# USB-UART_FT230XS_double-sided.net
KiCad netlist of a schematic drawn in EAGLE
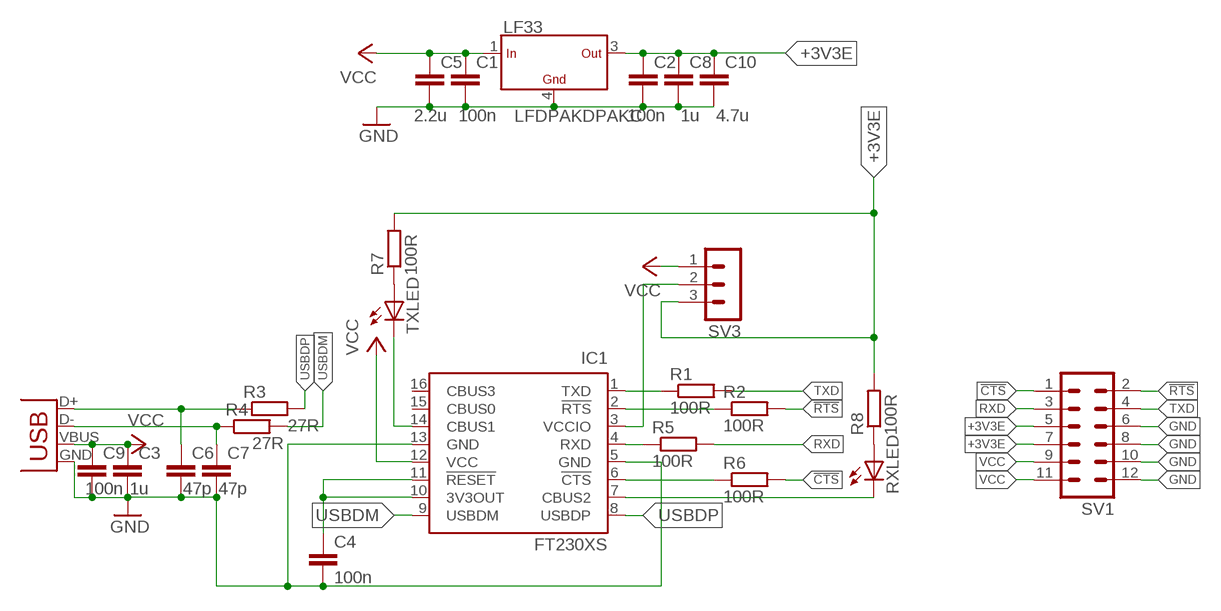
[diagram p0: schematic, sheet 1]

(export (version "E")
  (design (tool "Eeschema 10.0.6"))
  (components
    (comp (ref "C1")
      (value "100n")
      (footprint "eagle-import:C0805")
      (libsource (lib "eagle-import") (part "C-EUC0805"))
    )
    (comp (ref "C2")
      (value "100n")
      (footprint "eagle-import:C0805")
      (libsource (lib "eagle-import") (part "C-EUC0805"))
    )
    (comp (ref "C3")
      (value "1u")
      (footprint "eagle-import:C0805")
      (libsource (lib "eagle-import") (part "C-EUC0805"))
    )
    (comp (ref "C4")
      (value "100n")
      (footprint "eagle-import:C0805")
      (libsource (lib "eagle-import") (part "C-EUC0805"))
    )
    (comp (ref "C5")
      (value "2.2u")
      (footprint "eagle-import:C1206")
      (libsource (lib "eagle-import") (part "C-EUC1206"))
    )
    (comp (ref "C6")
      (value "47p")
      (footprint "eagle-import:C0805")
      (libsource (lib "eagle-import") (part "C-EUC0805"))
    )
    (comp (ref "C7")
      (value "47p")
      (footprint "eagle-import:C0805")
      (libsource (lib "eagle-import") (part "C-EUC0805"))
    )
    (comp (ref "C8")
      (value "1u")
      (footprint "eagle-import:C1206")
      (libsource (lib "eagle-import") (part "C-EUC1206"))
    )
    (comp (ref "C9")
      (value "100n")
      (footprint "eagle-import:C1206")
      (libsource (lib "eagle-import") (part "C-EUC1206"))
    )
    (comp (ref "C10")
      (value "4.7u")
      (footprint "eagle-import:C1206")
      (libsource (lib "eagle-import") (part "C-EUC1206"))
    )
    (comp (ref "IC1")
      (value "FT230XS")
      (footprint "eagle-import:SSOP16")
      (libsource (lib "eagle-import") (part "FT230XS"))
    )
    (comp (ref "LF33")
      (value "LFDPAKDPAKC")
      (footprint "eagle-import:DPAK")
      (libsource (lib "eagle-import") (part "LF??CDPAK"))
    )
    (comp (ref "R1")
      (value "100R")
      (footprint "eagle-import:M0805")
      (libsource (lib "eagle-import") (part "R-EU_M0805"))
    )
    (comp (ref "R2")
      (value "100R")
      (footprint "eagle-import:M0805")
      (libsource (lib "eagle-import") (part "R-EU_M0805"))
    )
    (comp (ref "R3")
      (value "27R")
      (footprint "eagle-import:M0805")
      (libsource (lib "eagle-import") (part "R-EU_M0805"))
    )
    (comp (ref "R4")
      (value "27R")
      (footprint "eagle-import:M0805")
      (libsource (lib "eagle-import") (part "R-EU_M0805"))
    )
    (comp (ref "R5")
      (value "100R")
      (footprint "eagle-import:M0805")
      (libsource (lib "eagle-import") (part "R-EU_M0805"))
    )
    (comp (ref "R6")
      (value "100R")
      (footprint "eagle-import:M0805")
      (libsource (lib "eagle-import") (part "R-EU_M0805"))
    )
    (comp (ref "R7")
      (value "100R")
      (footprint "eagle-import:M0805")
      (libsource (lib "eagle-import") (part "R-EU_M0805"))
    )
    (comp (ref "R8")
      (value "100R")
      (footprint "eagle-import:M0805")
      (libsource (lib "eagle-import") (part "R-EU_M0805"))
    )
    (comp (ref "RXLED")
      (value "LEDCHIP-LED0603")
      (footprint "eagle-import:CHIP-LED0603")
      (libsource (lib "eagle-import") (part "LEDCHIP-LED0603"))
    )
    (comp (ref "SV1")
      (value "MA06-2")
      (footprint "eagle-import:MA06-2")
      (libsource (lib "eagle-import") (part "MA06-2"))
    )
    (comp (ref "SV3")
      (value "MA03-1")
      (footprint "eagle-import:MA03-1")
      (libsource (lib "eagle-import") (part "MA03-1"))
    )
    (comp (ref "TXLED")
      (value "LEDCHIP-LED0603")
      (footprint "eagle-import:CHIP-LED0603")
      (libsource (lib "eagle-import") (part "LEDCHIP-LED0603"))
    )
    (comp (ref "X1")
      (value "USBSMD")
      (footprint "eagle-import:USB-MINIB")
      (libsource (lib "eagle-import") (part "USBSMD"))
    )
  )
  (nets
    (net (code "1") (name "+3V3E") (class "Default")
      (node (ref "C10") (pin "1") (pinfunction "1_1") (pintype "passive"))
      (node (ref "C2") (pin "1") (pinfunction "1_1") (pintype "passive"))
      (node (ref "C8") (pin "1") (pinfunction "1_1") (pintype "passive"))
      (node (ref "LF33") (pin "3") (pinfunction "OUT_3") (pintype "passive"))
      (node (ref "R7") (pin "2") (pinfunction "2_2") (pintype "passive"))
      (node (ref "R8") (pin "2") (pinfunction "2_2") (pintype "passive"))
      (node (ref "SV1") (pin "5") (pinfunction "5_5") (pintype "passive"))
      (node (ref "SV1") (pin "7") (pinfunction "7_7") (pintype "passive"))
      (node (ref "SV3") (pin "3") (pinfunction "3_3") (pintype "passive"))
    )
    (net (code "2") (name "/~{CTS}") (class "Default")
      (node (ref "R6") (pin "2") (pinfunction "2_2") (pintype "passive"))
      (node (ref "SV1") (pin "1") (pinfunction "1_1") (pintype "passive"))
    )
    (net (code "3") (name "/~{RTS}") (class "Default")
      (node (ref "R2") (pin "2") (pinfunction "2_2") (pintype "passive"))
      (node (ref "SV1") (pin "2") (pinfunction "2_2") (pintype "passive"))
    )
    (net (code "4") (name "GND") (class "Default")
      (node (ref "C1") (pin "2") (pinfunction "2_2") (pintype "passive"))
      (node (ref "C10") (pin "2") (pinfunction "2_2") (pintype "passive"))
      (node (ref "C2") (pin "2") (pinfunction "2_2") (pintype "passive"))
      (node (ref "C3") (pin "2") (pinfunction "2_2") (pintype "passive"))
      (node (ref "C4") (pin "2") (pinfunction "2_2") (pintype "passive"))
      (node (ref "C5") (pin "2") (pinfunction "2_2") (pintype "passive"))
      (node (ref "C6") (pin "2") (pinfunction "2_2") (pintype "passive"))
      (node (ref "C7") (pin "2") (pinfunction "2_2") (pintype "passive"))
      (node (ref "C8") (pin "2") (pinfunction "2_2") (pintype "passive"))
      (node (ref "C9") (pin "2") (pinfunction "2_2") (pintype "passive"))
      (node (ref "IC1") (pin "13") (pinfunction "GND_13") (pintype "power_in"))
      (node (ref "IC1") (pin "5") (pinfunction "GND_5") (pintype "power_in"))
      (node (ref "LF33") (pin "4") (pinfunction "GND_4") (pintype "passive"))
      (node (ref "SV1") (pin "10") (pinfunction "10_10") (pintype "passive"))
      (node (ref "SV1") (pin "12") (pinfunction "12_12") (pintype "passive"))
      (node (ref "SV1") (pin "6") (pinfunction "6_6") (pintype "passive"))
      (node (ref "SV1") (pin "8") (pinfunction "8_8") (pintype "passive"))
      (node (ref "X1") (pin "GND") (pinfunction "GND_GND") (pintype "bidirectional"))
    )
    (net (code "5") (name "Net-(C6-Pad1)") (class "Default")
      (node (ref "C6") (pin "1") (pinfunction "1_1") (pintype "passive"))
      (node (ref "R3") (pin "1") (pinfunction "1_1") (pintype "passive"))
      (node (ref "X1") (pin "D+") (pinfunction "D+_D+") (pintype "bidirectional"))
    )
    (net (code "6") (name "Net-(C7-Pad1)") (class "Default")
      (node (ref "C7") (pin "1") (pinfunction "1_1") (pintype "passive"))
      (node (ref "R4") (pin "1") (pinfunction "1_1") (pintype "passive"))
      (node (ref "X1") (pin "D-") (pinfunction "D-_D-") (pintype "bidirectional"))
    )
    (net (code "7") (name "Net-(IC1-3V3OUT)") (class "Default")
      (node (ref "C4") (pin "1") (pinfunction "1_1") (pintype "passive"))
      (node (ref "IC1") (pin "10") (pinfunction "3V3OUT_10") (pintype "output"))
      (node (ref "IC1") (pin "11") (pinfunction "~{RESET}_11") (pintype "input"))
    )
    (net (code "8") (name "Net-(IC1-CBUS1)") (class "Default")
      (node (ref "IC1") (pin "14") (pinfunction "CBUS1_14") (pintype "bidirectional"))
      (node (ref "TXLED") (pin "C") (pinfunction "C_C") (pintype "passive"))
    )
    (net (code "9") (name "Net-(IC1-CBUS2)") (class "Default")
      (node (ref "IC1") (pin "7") (pinfunction "CBUS2_7") (pintype "bidirectional"))
      (node (ref "RXLED") (pin "C") (pinfunction "C_C") (pintype "passive"))
    )
    (net (code "10") (name "Net-(IC1-RXD)") (class "Default")
      (node (ref "IC1") (pin "4") (pinfunction "RXD_4") (pintype "input"))
      (node (ref "R5") (pin "1") (pinfunction "1_1") (pintype "passive"))
    )
    (net (code "11") (name "Net-(IC1-TXD)") (class "Default")
      (node (ref "IC1") (pin "1") (pinfunction "TXD_1") (pintype "output"))
      (node (ref "R1") (pin "1") (pinfunction "1_1") (pintype "passive"))
    )
    (net (code "12") (name "Net-(IC1-VCCIO)") (class "Default")
      (node (ref "IC1") (pin "3") (pinfunction "VCCIO_3") (pintype "power_in"))
      (node (ref "SV3") (pin "2") (pinfunction "2_2") (pintype "passive"))
    )
    (net (code "13") (name "Net-(IC1-~{CTS})") (class "Default")
      (node (ref "IC1") (pin "6") (pinfunction "~{CTS}_6") (pintype "input"))
      (node (ref "R6") (pin "1") (pinfunction "1_1") (pintype "passive"))
    )
    (net (code "14") (name "Net-(IC1-~{RTS})") (class "Default")
      (node (ref "IC1") (pin "2") (pinfunction "~{RTS}_2") (pintype "output"))
      (node (ref "R2") (pin "1") (pinfunction "1_1") (pintype "passive"))
    )
    (net (code "15") (name "Net-(R7-Pad1)") (class "Default")
      (node (ref "R7") (pin "1") (pinfunction "1_1") (pintype "passive"))
      (node (ref "TXLED") (pin "A") (pinfunction "A_A") (pintype "passive"))
    )
    (net (code "16") (name "Net-(R8-Pad1)") (class "Default")
      (node (ref "R8") (pin "1") (pinfunction "1_1") (pintype "passive"))
      (node (ref "RXLED") (pin "A") (pinfunction "A_A") (pintype "passive"))
    )
    (net (code "17") (name "RXD") (class "Default")
      (node (ref "R5") (pin "2") (pinfunction "2_2") (pintype "passive"))
      (node (ref "SV1") (pin "3") (pinfunction "3_3") (pintype "passive"))
    )
    (net (code "18") (name "TXD") (class "Default")
      (node (ref "R1") (pin "2") (pinfunction "2_2") (pintype "passive"))
      (node (ref "SV1") (pin "4") (pinfunction "4_4") (pintype "passive"))
    )
    (net (code "19") (name "USBDM") (class "Default")
      (node (ref "IC1") (pin "9") (pinfunction "USBDM_9") (pintype "input"))
      (node (ref "R4") (pin "2") (pinfunction "2_2") (pintype "passive"))
    )
    (net (code "20") (name "USBDP") (class "Default")
      (node (ref "IC1") (pin "8") (pinfunction "USBDP_8") (pintype "input"))
      (node (ref "R3") (pin "2") (pinfunction "2_2") (pintype "passive"))
    )
    (net (code "21") (name "VCC") (class "Default")
      (node (ref "C1") (pin "1") (pinfunction "1_1") (pintype "passive"))
      (node (ref "C3") (pin "1") (pinfunction "1_1") (pintype "passive"))
      (node (ref "C5") (pin "1") (pinfunction "1_1") (pintype "passive"))
      (node (ref "C9") (pin "1") (pinfunction "1_1") (pintype "passive"))
      (node (ref "IC1") (pin "12") (pinfunction "VCC_12") (pintype "power_in"))
      (node (ref "LF33") (pin "1") (pinfunction "IN_1") (pintype "passive"))
      (node (ref "SV1") (pin "11") (pinfunction "11_11") (pintype "passive"))
      (node (ref "SV1") (pin "9") (pinfunction "9_9") (pintype "passive"))
      (node (ref "SV3") (pin "1") (pinfunction "1_1") (pintype "passive"))
      (node (ref "X1") (pin "VBUS") (pinfunction "VBUS_VBUS") (pintype "bidirectional"))
    )
    (net (code "22") (name "unconnected-(IC1-CBUS0-Pad15)") (class "Default")
      (node (ref "IC1") (pin "15") (pinfunction "CBUS0_15") (pintype "bidirectional"))
    )
    (net (code "23") (name "unconnected-(IC1-CBUS3-Pad16)") (class "Default")
      (node (ref "IC1") (pin "16") (pinfunction "CBUS3_16") (pintype "bidirectional"))
    )
  )
)
